# pir.net
KiCad netlist of a schematic drawn in Altium Designer
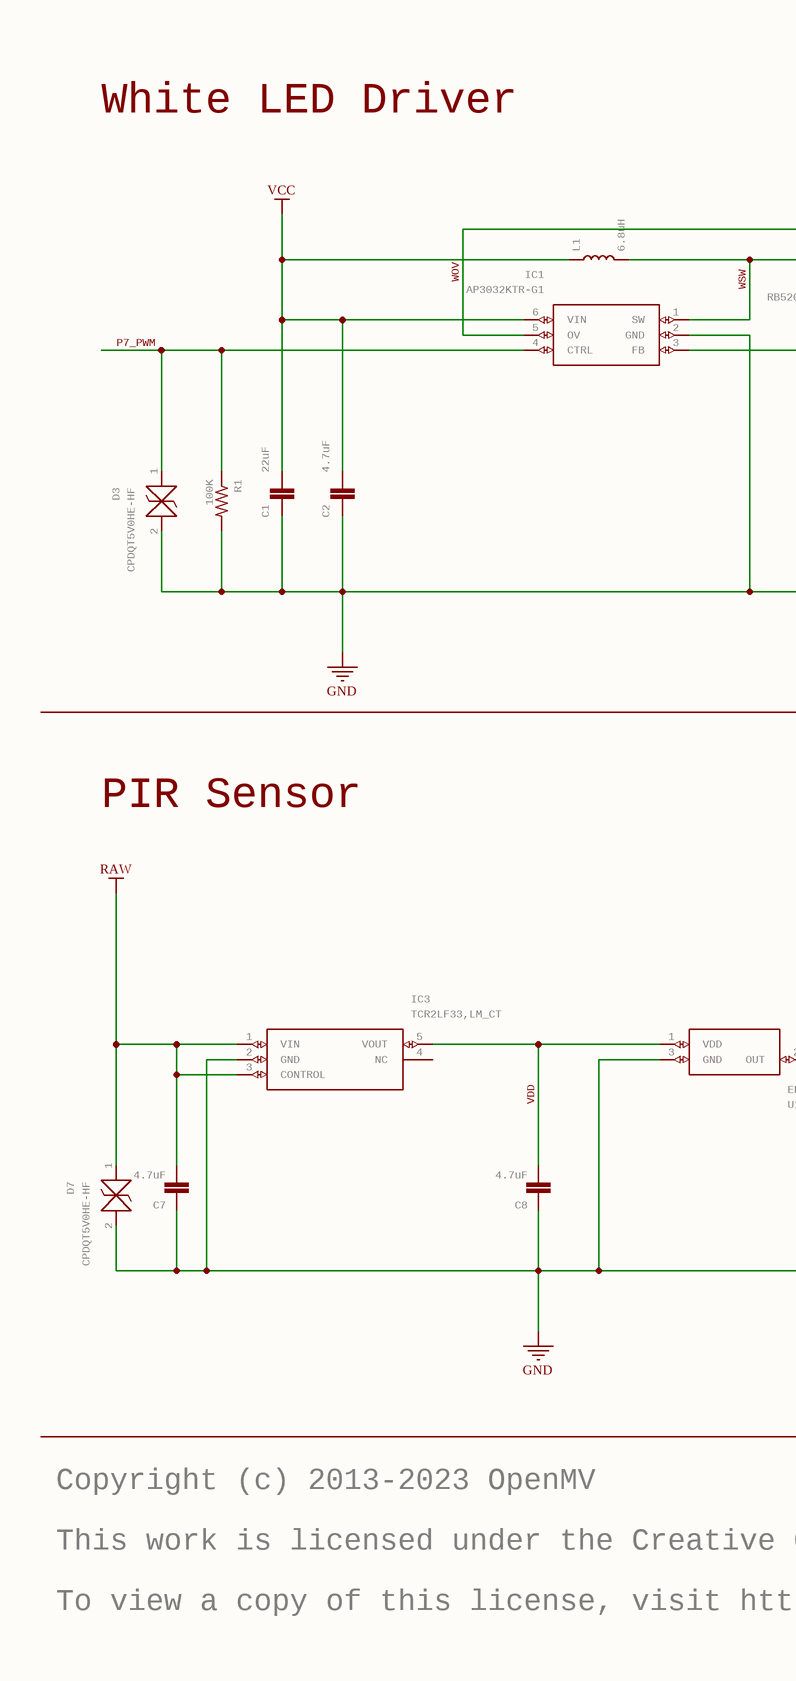
[diagram p0: pir.SchDoc, left]
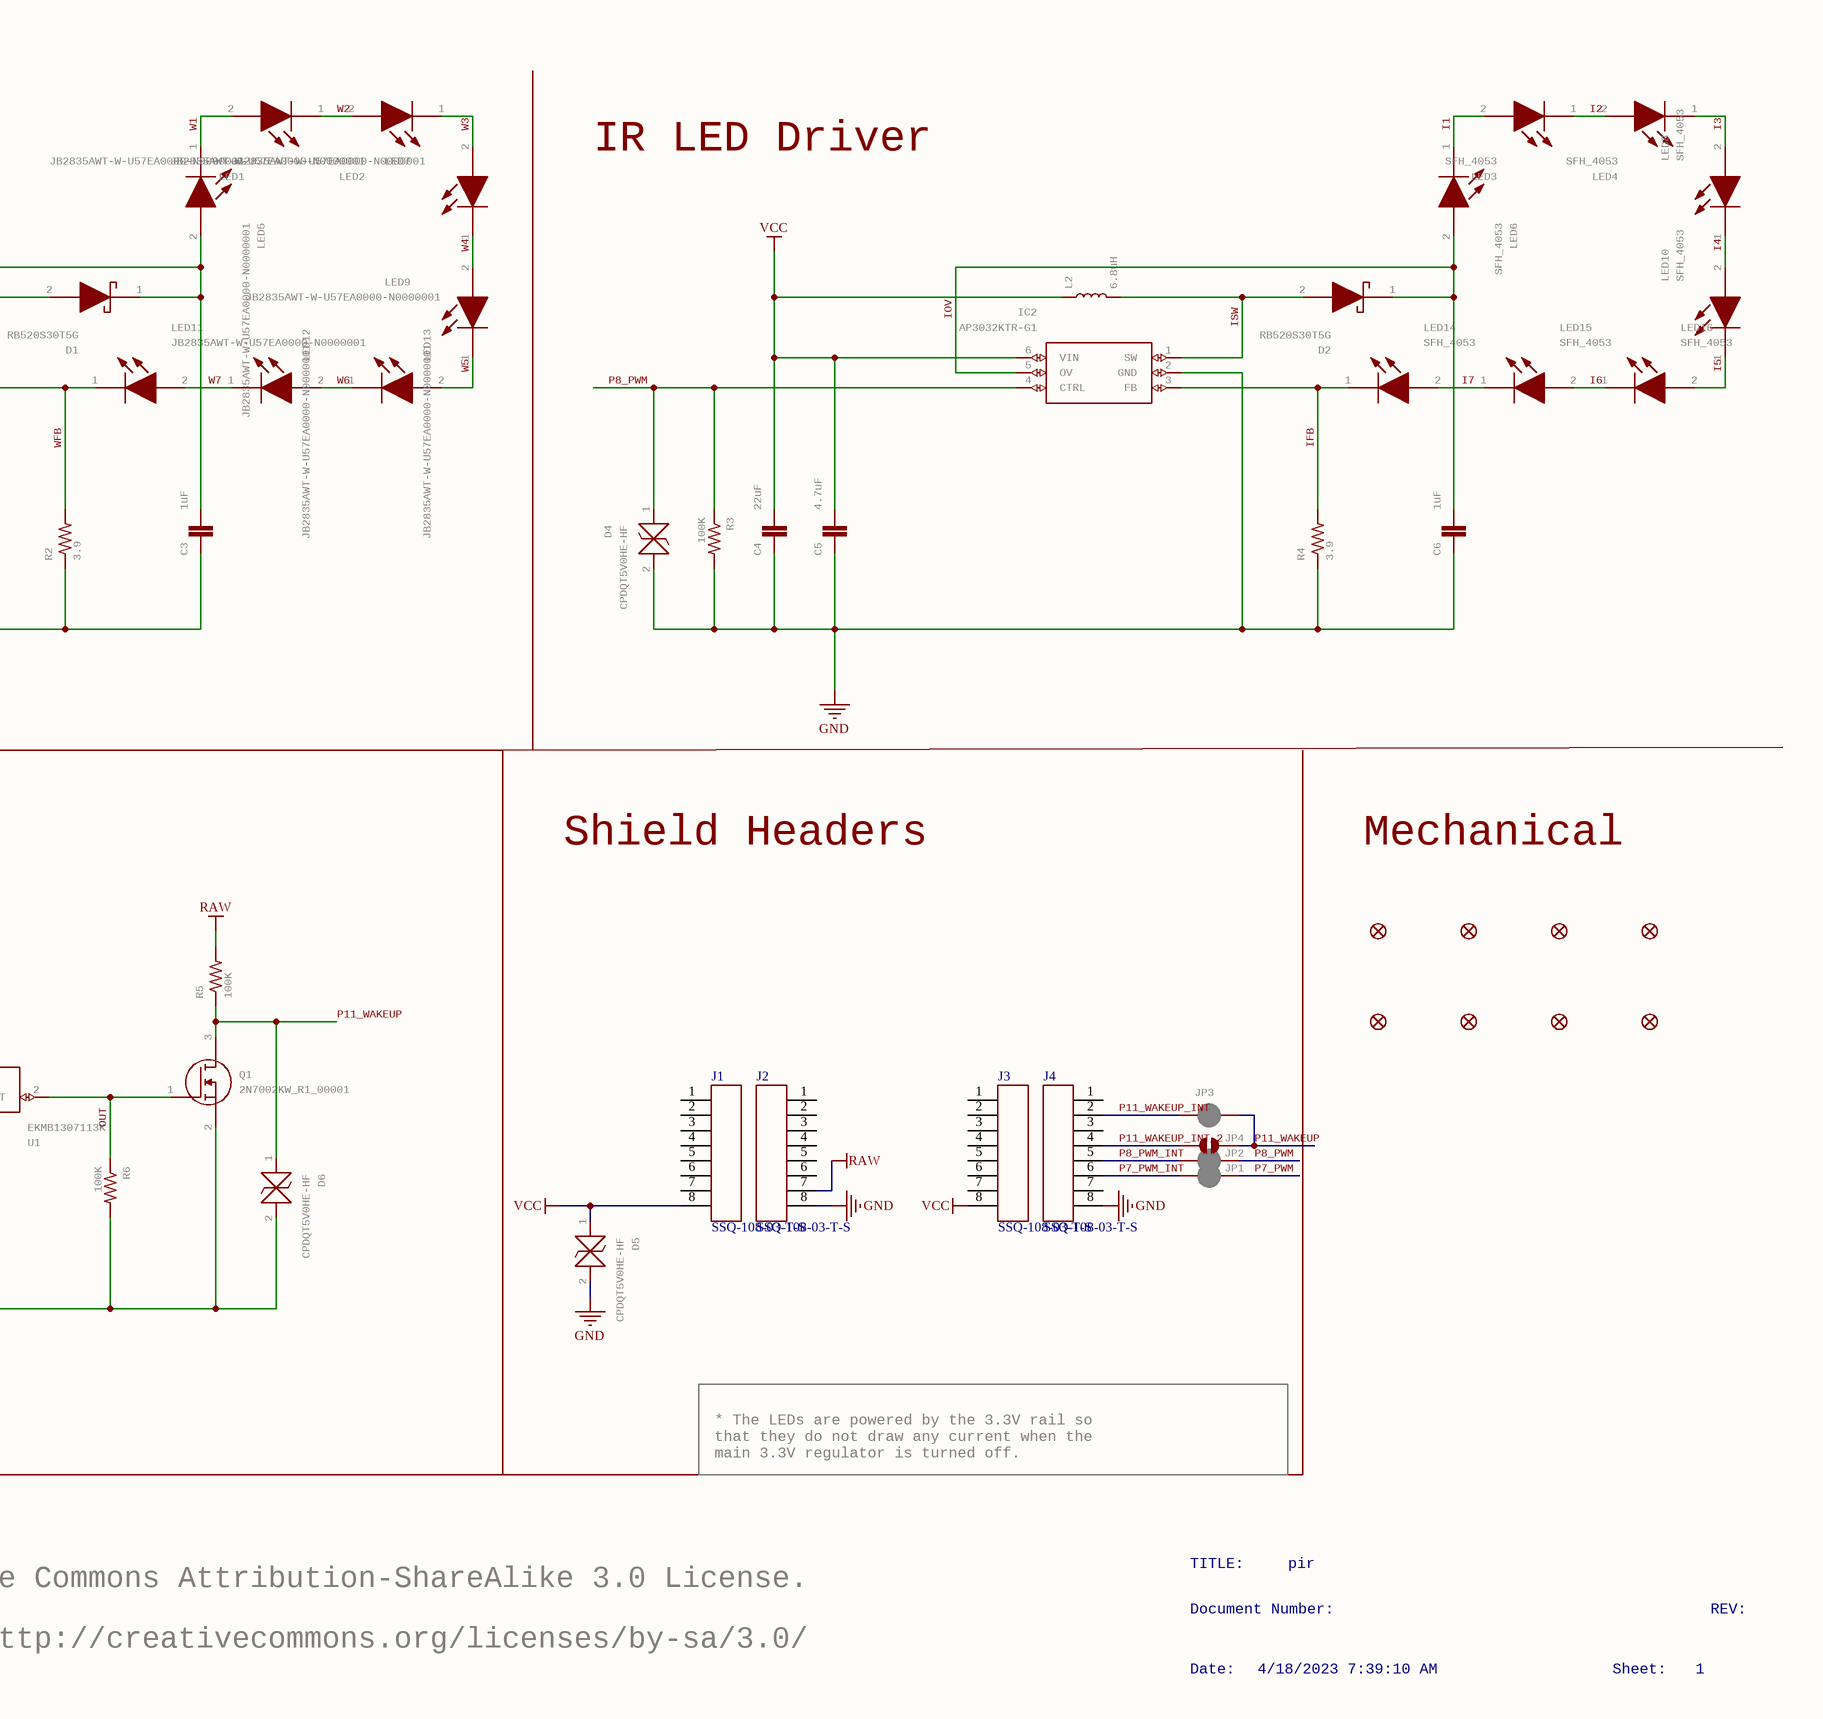
[diagram p1: pir.SchDoc, right]

(export (version "E")
  (design (tool "Eeschema 10.0.6"))
  (components
    (comp (ref "C1")
      (value "22uF")
      (footprint "0805")
      (fields (field (name "MPN") "CL21A226MQQNNNE"))
      (libsource (lib "pir") (part "22UF-0805-6.3V-20%"))
    )
    (comp (ref "C2")
      (value "4.7uF")
      (footprint "0402-CAP")
      (description "CapacitorStandard 0603 ceramic capacitor, and 0.1\" leaded capacitor.")
      (fields (field (name "MPN") "JMK105BBJ475MV-F"))
      (libsource (lib "pir") (part "CAP0402-CAP"))
    )
    (comp (ref "C3")
      (value "1uF")
      (footprint "0402-CAP")
      (description "CapacitorStandard 0603 ceramic capacitor, and 0.1\" leaded capacitor.")
      (fields (field (name "MPN") "GRM155R6YA105KE11D"))
      (libsource (lib "pir") (part "CAP0402-CAP"))
    )
    (comp (ref "C4")
      (value "22uF")
      (footprint "0805")
      (fields (field (name "MPN") "CL21A226MQQNNNE"))
      (libsource (lib "pir") (part "22UF-0805-6.3V-20%"))
    )
    (comp (ref "C5")
      (value "4.7uF")
      (footprint "0402-CAP")
      (description "CapacitorStandard 0603 ceramic capacitor, and 0.1\" leaded capacitor.")
      (fields (field (name "MPN") "JMK105BBJ475MV-F"))
      (libsource (lib "pir") (part "CAP0402-CAP"))
    )
    (comp (ref "C6")
      (value "1uF")
      (footprint "0402-CAP")
      (description "CapacitorStandard 0603 ceramic capacitor, and 0.1\" leaded capacitor.")
      (fields (field (name "MPN") "GRM155R6YA105KE11D"))
      (libsource (lib "pir") (part "CAP0402-CAP"))
    )
    (comp (ref "C7")
      (value "4.7uF")
      (footprint "0402-CAP")
      (description "CapacitorStandard 0603 ceramic capacitor, and 0.1\" leaded capacitor.")
      (fields (field (name "MPN") "JMK105BBJ475MV-F"))
      (libsource (lib "pir") (part "CAP0402-CAP"))
    )
    (comp (ref "C8")
      (value "4.7uF")
      (footprint "0402-CAP")
      (description "CapacitorStandard 0603 ceramic capacitor, and 0.1\" leaded capacitor.")
      (fields (field (name "MPN") "JMK105BBJ475MV-F"))
      (libsource (lib "pir") (part "CAP0402-CAP"))
    )
    (comp (ref "D1")
      (value "RB520S30T5G")
      (footprint "SODFL1608X70N")
      (description "Diode Schottky 30V 0.2A Automotive 2-Pin SOD-523 T/R   Source:  Datasheet")
      (fields (field (name "MOUSER_PART_NUMBER") "863-RB520S30T5G"))
      (libsource (lib "pir") (part "RB520S30T5G"))
    )
    (comp (ref "D2")
      (value "RB520S30T5G")
      (footprint "SODFL1608X70N")
      (description "Diode Schottky 30V 0.2A Automotive 2-Pin SOD-523 T/R   Source:  Datasheet")
      (fields (field (name "MOUSER_PART_NUMBER") "863-RB520S30T5G"))
      (libsource (lib "pir") (part "RB520S30T5G"))
    )
    (comp (ref "D3")
      (value "CPDQT5V0HE-HF")
      (footprint "CPDQT5V0HEHF")
      (description "ESD Suppressors / TVS Diodes DIODE ESD 5VWM 65W 0402/SOD-923F   Source:  Datasheet")
      (fields (field (name "MOUSER_PART_NUMBER") "MOUSER_PART_NUMBER"))
      (libsource (lib "pir") (part "CPDQT5V0HE-HF"))
    )
    (comp (ref "D4")
      (value "CPDQT5V0HE-HF")
      (footprint "CPDQT5V0HEHF")
      (description "ESD Suppressors / TVS Diodes DIODE ESD 5VWM 65W 0402/SOD-923F   Source:  Datasheet")
      (fields (field (name "MOUSER_PART_NUMBER") "MOUSER_PART_NUMBER"))
      (libsource (lib "pir") (part "CPDQT5V0HE-HF"))
    )
    (comp (ref "D5")
      (value "CPDQT5V0HE-HF")
      (footprint "CPDQT5V0HEHF")
      (description "ESD Suppressors / TVS Diodes DIODE ESD 5VWM 65W 0402/SOD-923F   Source:  Datasheet")
      (fields (field (name "MOUSER_PART_NUMBER") "MOUSER_PART_NUMBER"))
      (libsource (lib "pir") (part "CPDQT5V0HE-HF"))
    )
    (comp (ref "D6")
      (value "CPDQT5V0HE-HF")
      (footprint "CPDQT5V0HEHF")
      (description "ESD Suppressors / TVS Diodes DIODE ESD 5VWM 65W 0402/SOD-923F   Source:  Datasheet")
      (fields (field (name "MOUSER_PART_NUMBER") "MOUSER_PART_NUMBER"))
      (libsource (lib "pir") (part "CPDQT5V0HE-HF"))
    )
    (comp (ref "D7")
      (value "CPDQT5V0HE-HF")
      (footprint "CPDQT5V0HEHF")
      (description "ESD Suppressors / TVS Diodes DIODE ESD 5VWM 65W 0402/SOD-923F   Source:  Datasheet")
      (fields (field (name "MOUSER_PART_NUMBER") "MOUSER_PART_NUMBER"))
      (libsource (lib "pir") (part "CPDQT5V0HE-HF"))
    )
    (comp (ref "FD1")
      (value "FIDUCIAL1X2")
      (footprint "FIDUCIAL-1X2")
      (fields (field (name "LIBRARYNAME") "SparkFun-Aesthetics"))
      (libsource (lib "pir") (part "FIDUCIAL1X2"))
    )
    (comp (ref "FD2")
      (value "FIDUCIAL1X2")
      (footprint "FIDUCIAL-1X2")
      (fields (field (name "LIBRARYNAME") "SparkFun-Aesthetics"))
      (libsource (lib "pir") (part "FIDUCIAL1X2"))
    )
    (comp (ref "FD3")
      (value "FIDUCIAL1X2")
      (footprint "FIDUCIAL-1X2")
      (fields (field (name "LIBRARYNAME") "SparkFun-Aesthetics"))
      (libsource (lib "pir") (part "FIDUCIAL1X2"))
    )
    (comp (ref "FD4")
      (value "FIDUCIAL1X2")
      (footprint "FIDUCIAL-1X2")
      (fields (field (name "LIBRARYNAME") "SparkFun-Aesthetics"))
      (libsource (lib "pir") (part "FIDUCIAL1X2"))
    )
    (comp (ref "FD5")
      (value "FIDUCIAL1X2")
      (footprint "FIDUCIAL-1X2")
      (fields (field (name "LIBRARYNAME") "SparkFun-Aesthetics"))
      (libsource (lib "pir") (part "FIDUCIAL1X2"))
    )
    (comp (ref "FD6")
      (value "FIDUCIAL1X2")
      (footprint "FIDUCIAL-1X2")
      (fields (field (name "LIBRARYNAME") "SparkFun-Aesthetics"))
      (libsource (lib "pir") (part "FIDUCIAL1X2"))
    )
    (comp (ref "FD7")
      (value "FIDUCIAL1X2")
      (footprint "FIDUCIAL-1X2")
      (fields (field (name "LIBRARYNAME") "SparkFun-Aesthetics"))
      (libsource (lib "pir") (part "FIDUCIAL1X2"))
    )
    (comp (ref "FD8")
      (value "FIDUCIAL1X2")
      (footprint "FIDUCIAL-1X2")
      (fields (field (name "LIBRARYNAME") "SparkFun-Aesthetics"))
      (libsource (lib "pir") (part "FIDUCIAL1X2"))
    )
    (comp (ref "IC1")
      (value "AP3032KTR-G1")
      (footprint "SOT95P280X145-6N")
      (fields (field (name "MOUSER_PART_NUMBER") "621-AP3032KTR-G1"))
      (libsource (lib "pir") (part "AP3032KTR-G1"))
    )
    (comp (ref "IC2")
      (value "AP3032KTR-G1")
      (footprint "SOT95P280X145-6N")
      (fields (field (name "MOUSER_PART_NUMBER") "621-AP3032KTR-G1"))
      (libsource (lib "pir") (part "AP3032KTR-G1"))
    )
    (comp (ref "IC3")
      (value "TCR2LF33,LM_CT")
      (footprint "TCR2LF33LMCT")
      (description "Linear Voltage Regulator IC Positive Fixed 1 Output 200mA SMV   Source:  Datasheet")
      (fields
        (field (name "MANUFACTURER_PART_NUMBER") "TCR2LF33,LM(CT")
        (field (name "MOUSER_PART_NUMBER") "757-TCR2LF33LMCT")
      )
      (libsource (lib "pir") (part "TCR2LF33,LM_CT"))
    )
    (comp (ref "J1") (value "SSQ-108-03-T-S") (footprint "HDR_1X8") (libsource (lib "") (part "HDR_1X8_1")))
    (comp (ref "J2") (value "SSQ-108-03-T-S") (footprint "HDR_1X8") (libsource (lib "pir") (part "HDR_1X8")))
    (comp (ref "J3") (value "SSQ-108-03-T-S") (footprint "HDR_1X8") (libsource (lib "") (part "HDR_1X8_1")))
    (comp (ref "J4") (value "SSQ-108-03-T-S") (footprint "HDR_1X8") (libsource (lib "pir") (part "HDR_1X8")))
    (comp (ref "JP1")
      (value "JUMPER-SMT_2_NC_PASTE_SILK")
      (footprint "SMT-JUMPER_2_NC_PASTE_SILK")
      (libsource (lib "pir") (part "JUMPER-SMT_2_NC_PASTE_SILK"))
    )
    (comp (ref "JP2")
      (value "JUMPER-SMT_2_NC_PASTE_SILK")
      (footprint "SMT-JUMPER_2_NC_PASTE_SILK")
      (libsource (lib "pir") (part "JUMPER-SMT_2_NC_PASTE_SILK"))
    )
    (comp (ref "JP3")
      (value "JUMPER-SMT_2_NC_PASTE_SILK")
      (footprint "SMT-JUMPER_2_NC_PASTE_SILK")
      (libsource (lib "pir") (part "JUMPER-SMT_2_NC_PASTE_SILK"))
    )
    (comp (ref "JP4")
      (value "JUMPER-SMT_2_NO_SILK")
      (footprint "SMT-JUMPER_2_NO_SILK")
      (libsource (lib "pir") (part "JUMPER-SMT_2_NO_SILK"))
    )
    (comp (ref "L1")
      (value "6.8uH")
      (footprint "0805")
      (fields (field (name "MPN") "MLZ2012M6R8WT000") (field (name "LIBRARYNAME") "SparkFun-Coils"))
      (libsource (lib "pir") (part "INDUCTOR-0805-3.3UH"))
    )
    (comp (ref "L2")
      (value "6.8uH")
      (footprint "0805")
      (fields (field (name "MPN") "MLZ2012M6R8WT000") (field (name "LIBRARYNAME") "SparkFun-Coils"))
      (libsource (lib "pir") (part "INDUCTOR-0805-3.3UH"))
    )
    (comp (ref "LED1")
      (value "JB2835AWT-W-U57EA0000-N0000001")
      (footprint "JB2835AWTWU57EA0000N0000001")
      (description "Mid-Power LEDs - White White 5700 K 90-CRI, 2835 Size, W Class   Source:  Datasheet")
      (fields (field (name "MOUSER_PART_NUMBER") "941-JB2835AWTU57EAN"))
      (libsource (lib "pir") (part "JB2835AWT-W-U57EA0000-N0000001"))
    )
    (comp (ref "LED2")
      (value "JB2835AWT-W-U57EA0000-N0000001")
      (footprint "JB2835AWTWU57EA0000N0000001")
      (description "Mid-Power LEDs - White White 5700 K 90-CRI, 2835 Size, W Class   Source:  Datasheet")
      (fields (field (name "MOUSER_PART_NUMBER") "941-JB2835AWTU57EAN"))
      (libsource (lib "pir") (part "JB2835AWT-W-U57EA0000-N0000001"))
    )
    (comp (ref "LED3")
      (value "SFH_4053")
      (footprint "LEDC1005X55N")
      (fields
        (field (name "MANUFACTURER_PART_NUMBER") "SFH 4053")
        (field (name "MOUSER_PART_NUMBER") "720-SFH4053")
      )
      (libsource (lib "pir") (part "SFH_4053"))
    )
    (comp (ref "LED4")
      (value "SFH_4053")
      (footprint "LEDC1005X55N")
      (fields
        (field (name "MANUFACTURER_PART_NUMBER") "SFH 4053")
        (field (name "MOUSER_PART_NUMBER") "720-SFH4053")
      )
      (libsource (lib "pir") (part "SFH_4053"))
    )
    (comp (ref "LED5")
      (value "JB2835AWT-W-U57EA0000-N0000001")
      (footprint "JB2835AWTWU57EA0000N0000001")
      (description "Mid-Power LEDs - White White 5700 K 90-CRI, 2835 Size, W Class   Source:  Datasheet")
      (fields (field (name "MOUSER_PART_NUMBER") "941-JB2835AWTU57EAN"))
      (libsource (lib "pir") (part "JB2835AWT-W-U57EA0000-N0000001"))
    )
    (comp (ref "LED6")
      (value "SFH_4053")
      (footprint "LEDC1005X55N")
      (fields
        (field (name "MANUFACTURER_PART_NUMBER") "SFH 4053")
        (field (name "MOUSER_PART_NUMBER") "720-SFH4053")
      )
      (libsource (lib "pir") (part "SFH_4053"))
    )
    (comp (ref "LED7")
      (value "JB2835AWT-W-U57EA0000-N0000001")
      (footprint "JB2835AWTWU57EA0000N0000001")
      (description "Mid-Power LEDs - White White 5700 K 90-CRI, 2835 Size, W Class   Source:  Datasheet")
      (fields (field (name "MOUSER_PART_NUMBER") "941-JB2835AWTU57EAN"))
      (libsource (lib "pir") (part "JB2835AWT-W-U57EA0000-N0000001"))
    )
    (comp (ref "LED8")
      (value "SFH_4053")
      (footprint "LEDC1005X55N")
      (fields
        (field (name "MANUFACTURER_PART_NUMBER") "SFH 4053")
        (field (name "MOUSER_PART_NUMBER") "720-SFH4053")
      )
      (libsource (lib "pir") (part "SFH_4053"))
    )
    (comp (ref "LED9")
      (value "JB2835AWT-W-U57EA0000-N0000001")
      (footprint "JB2835AWTWU57EA0000N0000001")
      (description "Mid-Power LEDs - White White 5700 K 90-CRI, 2835 Size, W Class   Source:  Datasheet")
      (fields (field (name "MOUSER_PART_NUMBER") "941-JB2835AWTU57EAN"))
      (libsource (lib "pir") (part "JB2835AWT-W-U57EA0000-N0000001"))
    )
    (comp (ref "LED10")
      (value "SFH_4053")
      (footprint "LEDC1005X55N")
      (fields
        (field (name "MANUFACTURER_PART_NUMBER") "SFH 4053")
        (field (name "MOUSER_PART_NUMBER") "720-SFH4053")
      )
      (libsource (lib "pir") (part "SFH_4053"))
    )
    (comp (ref "LED11")
      (value "JB2835AWT-W-U57EA0000-N0000001")
      (footprint "JB2835AWTWU57EA0000N0000001")
      (description "Mid-Power LEDs - White White 5700 K 90-CRI, 2835 Size, W Class   Source:  Datasheet")
      (fields (field (name "MOUSER_PART_NUMBER") "941-JB2835AWTU57EAN"))
      (libsource (lib "pir") (part "JB2835AWT-W-U57EA0000-N0000001"))
    )
    (comp (ref "LED12")
      (value "JB2835AWT-W-U57EA0000-N0000001")
      (footprint "JB2835AWTWU57EA0000N0000001")
      (description "Mid-Power LEDs - White White 5700 K 90-CRI, 2835 Size, W Class   Source:  Datasheet")
      (fields (field (name "MOUSER_PART_NUMBER") "941-JB2835AWTU57EAN"))
      (libsource (lib "pir") (part "JB2835AWT-W-U57EA0000-N0000001"))
    )
    (comp (ref "LED13")
      (value "JB2835AWT-W-U57EA0000-N0000001")
      (footprint "JB2835AWTWU57EA0000N0000001")
      (description "Mid-Power LEDs - White White 5700 K 90-CRI, 2835 Size, W Class   Source:  Datasheet")
      (fields (field (name "MOUSER_PART_NUMBER") "941-JB2835AWTU57EAN"))
      (libsource (lib "pir") (part "JB2835AWT-W-U57EA0000-N0000001"))
    )
    (comp (ref "LED14")
      (value "SFH_4053")
      (footprint "LEDC1005X55N")
      (fields
        (field (name "MANUFACTURER_PART_NUMBER") "SFH 4053")
        (field (name "MOUSER_PART_NUMBER") "720-SFH4053")
      )
      (libsource (lib "pir") (part "SFH_4053"))
    )
    (comp (ref "LED15")
      (value "SFH_4053")
      (footprint "LEDC1005X55N")
      (fields
        (field (name "MANUFACTURER_PART_NUMBER") "SFH 4053")
        (field (name "MOUSER_PART_NUMBER") "720-SFH4053")
      )
      (libsource (lib "pir") (part "SFH_4053"))
    )
    (comp (ref "LED16")
      (value "SFH_4053")
      (footprint "LEDC1005X55N")
      (fields
        (field (name "MANUFACTURER_PART_NUMBER") "SFH 4053")
        (field (name "MOUSER_PART_NUMBER") "720-SFH4053")
      )
      (libsource (lib "pir") (part "SFH_4053"))
    )
    (comp (ref "Q1")
      (value "2N7002KW_R1_00001")
      (footprint "SOT65P210X110-3N")
      (description "MOSFET 60V N-Channel Enhancement Mode MOSFET - ESD Protected   Source:  Datasheet")
      (fields (field (name "MOUSER_PART_NUMBER") "241-2N7002KWR100001"))
      (libsource (lib "pir") (part "2N7002KW_R1_00001"))
    )
    (comp (ref "R1")
      (value "100K")
      (footprint "0402-RES")
      (description "ResistorBasic schematic elements and footprints for 0603, 1206, and PTH resistors.")
      (fields (field (name "MPN") "AC0402FR-07100KL"))
      (libsource (lib "pir") (part "RESISTOR0402-RES"))
    )
    (comp (ref "R2")
      (value "3.9")
      (footprint "R2512")
      (description "RESISTOR, American symbol")
      (fields (field (name "MPN") "35203R9JT"))
      (libsource (lib "pir") (part "R-US_R2512"))
    )
    (comp (ref "R3")
      (value "100K")
      (footprint "0402-RES")
      (description "ResistorBasic schematic elements and footprints for 0603, 1206, and PTH resistors.")
      (fields (field (name "MPN") "AC0402FR-07100KL"))
      (libsource (lib "pir") (part "RESISTOR0402-RES"))
    )
    (comp (ref "R4")
      (value "3.9")
      (footprint "R2512")
      (description "RESISTOR, American symbol")
      (fields (field (name "MPN") "35203R9JT"))
      (libsource (lib "pir") (part "R-US_R2512"))
    )
    (comp (ref "R5")
      (value "100K")
      (footprint "0402-RES")
      (description "ResistorBasic schematic elements and footprints for 0603, 1206, and PTH resistors.")
      (fields (field (name "MPN") "AC0402FR-07100KL"))
      (libsource (lib "pir") (part "RESISTOR0402-RES"))
    )
    (comp (ref "R6")
      (value "100K")
      (footprint "0402-RES")
      (description "ResistorBasic schematic elements and footprints for 0603, 1206, and PTH resistors.")
      (fields (field (name "MPN") "AC0402FR-07100KL"))
      (libsource (lib "pir") (part "RESISTOR0402-RES"))
    )
    (comp (ref "U1")
      (value "EKMB1307113K")
      (footprint "EKMB1304111K")
      (description "Sensor PIR (Passive Infrared) 472\" (12m) 39.4'  Module   Source:  Datasheet")
      (fields
        (field (name "MANUFACTURER_PART_NUMBER") "EKMB1304111K")
        (field (name "MOUSER_PART_NUMBER") "769-EKMB1304111K")
      )
      (libsource (lib "pir") (part "EKMB1304111K"))
    )
  )
  (nets
    (net (code "1") (name "/I1") (class "Default")
      (node (ref "LED3") (pin "2") (pinfunction "A_2") (pintype "bidirectional"))
      (node (ref "LED6") (pin "1") (pinfunction "K_1") (pintype "bidirectional"))
    )
    (net (code "2") (name "/I2") (class "Default")
      (node (ref "LED3") (pin "1") (pinfunction "K_1") (pintype "bidirectional"))
      (node (ref "LED4") (pin "2") (pinfunction "A_2") (pintype "bidirectional"))
    )
    (net (code "3") (name "/I3") (class "Default")
      (node (ref "LED4") (pin "1") (pinfunction "K_1") (pintype "bidirectional"))
      (node (ref "LED8") (pin "2") (pinfunction "A_2") (pintype "bidirectional"))
    )
    (net (code "4") (name "/I4") (class "Default")
      (node (ref "LED10") (pin "2") (pinfunction "A_2") (pintype "bidirectional"))
      (node (ref "LED8") (pin "1") (pinfunction "K_1") (pintype "bidirectional"))
    )
    (net (code "5") (name "/I5") (class "Default")
      (node (ref "LED10") (pin "1") (pinfunction "K_1") (pintype "bidirectional"))
      (node (ref "LED16") (pin "2") (pinfunction "A_2") (pintype "bidirectional"))
    )
    (net (code "6") (name "/I6") (class "Default")
      (node (ref "LED15") (pin "2") (pinfunction "A_2") (pintype "bidirectional"))
      (node (ref "LED16") (pin "1") (pinfunction "K_1") (pintype "bidirectional"))
    )
    (net (code "7") (name "/I7") (class "Default")
      (node (ref "LED14") (pin "2") (pinfunction "A_2") (pintype "bidirectional"))
      (node (ref "LED15") (pin "1") (pinfunction "K_1") (pintype "bidirectional"))
    )
    (net (code "8") (name "/IFB") (class "Default")
      (node (ref "IC2") (pin "3") (pinfunction "FB_3") (pintype "bidirectional"))
      (node (ref "LED14") (pin "1") (pinfunction "K_1") (pintype "bidirectional"))
      (node (ref "R4") (pin "2") (pinfunction "2_2") (pintype "passive"))
    )
    (net (code "9") (name "/IOV") (class "Default")
      (node (ref "C6") (pin "2") (pinfunction "2_2") (pintype "passive"))
      (node (ref "D2") (pin "1") (pinfunction "K_1") (pintype "bidirectional"))
      (node (ref "IC2") (pin "5") (pinfunction "OV_5") (pintype "bidirectional"))
      (node (ref "LED6") (pin "2") (pinfunction "A_2") (pintype "bidirectional"))
    )
    (net (code "10") (name "/ISW") (class "Default")
      (node (ref "D2") (pin "2") (pinfunction "A_2") (pintype "bidirectional"))
      (node (ref "IC2") (pin "1") (pinfunction "SW_1") (pintype "bidirectional"))
      (node (ref "L2") (pin "2") (pinfunction "2_2") (pintype "passive"))
    )
    (net (code "11") (name "/OUT") (class "Default")
      (node (ref "Q1") (pin "1") (pinfunction "G_1") (pintype "bidirectional"))
      (node (ref "R6") (pin "1") (pinfunction "1_1") (pintype "passive"))
      (node (ref "U1") (pin "2") (pinfunction "OUT_2") (pintype "bidirectional"))
    )
    (net (code "12") (name "/P7_PWM") (class "Default")
      (node (ref "D3") (pin "1") (pinfunction "1_1") (pintype "bidirectional"))
      (node (ref "IC1") (pin "4") (pinfunction "CTRL_4") (pintype "bidirectional"))
      (node (ref "JP1") (pin "2") (pinfunction "2_2") (pintype "passive"))
      (node (ref "R1") (pin "1") (pinfunction "1_1") (pintype "passive"))
    )
    (net (code "13") (name "/P7_PWM_INT") (class "Default")
      (node (ref "J4") (pin "6") (pintype "passive"))
      (node (ref "JP1") (pin "1") (pinfunction "1_1") (pintype "passive"))
    )
    (net (code "14") (name "/P8_PWM") (class "Default")
      (node (ref "D4") (pin "1") (pinfunction "1_1") (pintype "bidirectional"))
      (node (ref "IC2") (pin "4") (pinfunction "CTRL_4") (pintype "bidirectional"))
      (node (ref "JP2") (pin "2") (pinfunction "2_2") (pintype "passive"))
      (node (ref "R3") (pin "1") (pinfunction "1_1") (pintype "passive"))
    )
    (net (code "15") (name "/P8_PWM_INT") (class "Default")
      (node (ref "J4") (pin "5") (pintype "passive"))
      (node (ref "JP2") (pin "1") (pinfunction "1_1") (pintype "passive"))
    )
    (net (code "16") (name "/P11_WAKEUP") (class "Default")
      (node (ref "D6") (pin "1") (pinfunction "1_1") (pintype "bidirectional"))
      (node (ref "JP3") (pin "2") (pinfunction "2_2") (pintype "passive"))
      (node (ref "JP4") (pin "2") (pinfunction "2_2") (pintype "passive"))
      (node (ref "Q1") (pin "3") (pinfunction "D_3") (pintype "bidirectional"))
      (node (ref "R5") (pin "1") (pinfunction "1_1") (pintype "passive"))
    )
    (net (code "17") (name "/P11_WAKEUP_INT") (class "Default")
      (node (ref "J4") (pin "2") (pintype "passive"))
      (node (ref "JP3") (pin "1") (pinfunction "1_1") (pintype "passive"))
    )
    (net (code "18") (name "/P11_WAKEUP_INT_2") (class "Default")
      (node (ref "J4") (pin "4") (pintype "passive"))
      (node (ref "JP4") (pin "1") (pinfunction "1_1") (pintype "passive"))
    )
    (net (code "19") (name "/VDD") (class "Default")
      (node (ref "C8") (pin "2") (pinfunction "2_2") (pintype "passive"))
      (node (ref "IC3") (pin "5") (pinfunction "VOUT_5") (pintype "bidirectional"))
      (node (ref "U1") (pin "1") (pinfunction "VDD_1") (pintype "bidirectional"))
    )
    (net (code "20") (name "/W1") (class "Default")
      (node (ref "LED1") (pin "2") (pinfunction "A_2") (pintype "bidirectional"))
      (node (ref "LED5") (pin "1") (pinfunction "K_1") (pintype "bidirectional"))
    )
    (net (code "21") (name "/W2") (class "Default")
      (node (ref "LED1") (pin "1") (pinfunction "K_1") (pintype "bidirectional"))
      (node (ref "LED2") (pin "2") (pinfunction "A_2") (pintype "bidirectional"))
    )
    (net (code "22") (name "/W3") (class "Default")
      (node (ref "LED2") (pin "1") (pinfunction "K_1") (pintype "bidirectional"))
      (node (ref "LED7") (pin "2") (pinfunction "A_2") (pintype "bidirectional"))
    )
    (net (code "23") (name "/W4") (class "Default")
      (node (ref "LED7") (pin "1") (pinfunction "K_1") (pintype "bidirectional"))
      (node (ref "LED9") (pin "2") (pinfunction "A_2") (pintype "bidirectional"))
    )
    (net (code "24") (name "/W5") (class "Default")
      (node (ref "LED13") (pin "2") (pinfunction "A_2") (pintype "bidirectional"))
      (node (ref "LED9") (pin "1") (pinfunction "K_1") (pintype "bidirectional"))
    )
    (net (code "25") (name "/W6") (class "Default")
      (node (ref "LED12") (pin "2") (pinfunction "A_2") (pintype "bidirectional"))
      (node (ref "LED13") (pin "1") (pinfunction "K_1") (pintype "bidirectional"))
    )
    (net (code "26") (name "/W7") (class "Default")
      (node (ref "LED11") (pin "2") (pinfunction "A_2") (pintype "bidirectional"))
      (node (ref "LED12") (pin "1") (pinfunction "K_1") (pintype "bidirectional"))
    )
    (net (code "27") (name "/WFB") (class "Default")
      (node (ref "IC1") (pin "3") (pinfunction "FB_3") (pintype "bidirectional"))
      (node (ref "LED11") (pin "1") (pinfunction "K_1") (pintype "bidirectional"))
      (node (ref "R2") (pin "2") (pinfunction "2_2") (pintype "passive"))
    )
    (net (code "28") (name "/WOV") (class "Default")
      (node (ref "C3") (pin "2") (pinfunction "2_2") (pintype "passive"))
      (node (ref "D1") (pin "1") (pinfunction "K_1") (pintype "bidirectional"))
      (node (ref "IC1") (pin "5") (pinfunction "OV_5") (pintype "bidirectional"))
      (node (ref "LED5") (pin "2") (pinfunction "A_2") (pintype "bidirectional"))
    )
    (net (code "29") (name "/WSW") (class "Default")
      (node (ref "D1") (pin "2") (pinfunction "A_2") (pintype "bidirectional"))
      (node (ref "IC1") (pin "1") (pinfunction "SW_1") (pintype "bidirectional"))
      (node (ref "L1") (pin "2") (pinfunction "2_2") (pintype "passive"))
    )
    (net (code "30") (name "GND") (class "Default")
      (node (ref "C1") (pin "1") (pinfunction "1_1") (pintype "passive"))
      (node (ref "C2") (pin "1") (pinfunction "1_1") (pintype "passive"))
      (node (ref "C3") (pin "1") (pinfunction "1_1") (pintype "passive"))
      (node (ref "C4") (pin "1") (pinfunction "1_1") (pintype "passive"))
      (node (ref "C5") (pin "1") (pinfunction "1_1") (pintype "passive"))
      (node (ref "C6") (pin "1") (pinfunction "1_1") (pintype "passive"))
      (node (ref "C7") (pin "1") (pinfunction "1_1") (pintype "passive"))
      (node (ref "C8") (pin "1") (pinfunction "1_1") (pintype "passive"))
      (node (ref "D3") (pin "2") (pinfunction "2_2") (pintype "bidirectional"))
      (node (ref "D4") (pin "2") (pinfunction "2_2") (pintype "bidirectional"))
      (node (ref "D5") (pin "2") (pinfunction "2_2") (pintype "bidirectional"))
      (node (ref "D6") (pin "2") (pinfunction "2_2") (pintype "bidirectional"))
      (node (ref "D7") (pin "2") (pinfunction "2_2") (pintype "bidirectional"))
      (node (ref "IC1") (pin "2") (pinfunction "GND_2") (pintype "bidirectional"))
      (node (ref "IC2") (pin "2") (pinfunction "GND_2") (pintype "bidirectional"))
      (node (ref "IC3") (pin "2") (pinfunction "GND_2") (pintype "bidirectional"))
      (node (ref "J2") (pin "8") (pintype "passive"))
      (node (ref "J4") (pin "8") (pintype "passive"))
      (node (ref "Q1") (pin "2") (pinfunction "S_2") (pintype "bidirectional"))
      (node (ref "R1") (pin "2") (pinfunction "2_2") (pintype "passive"))
      (node (ref "R2") (pin "1") (pinfunction "1_1") (pintype "passive"))
      (node (ref "R3") (pin "2") (pinfunction "2_2") (pintype "passive"))
      (node (ref "R4") (pin "1") (pinfunction "1_1") (pintype "passive"))
      (node (ref "R6") (pin "2") (pinfunction "2_2") (pintype "passive"))
      (node (ref "U1") (pin "3") (pinfunction "GND_3") (pintype "bidirectional"))
    )
    (net (code "31") (name "RAW") (class "Default")
      (node (ref "C7") (pin "2") (pinfunction "2_2") (pintype "passive"))
      (node (ref "D7") (pin "1") (pinfunction "1_1") (pintype "bidirectional"))
      (node (ref "IC3") (pin "1") (pinfunction "VIN_1") (pintype "bidirectional"))
      (node (ref "IC3") (pin "3") (pinfunction "CONTROL_3") (pintype "bidirectional"))
      (node (ref "J2") (pin "7") (pintype "passive"))
      (node (ref "R5") (pin "2") (pinfunction "2_2") (pintype "passive"))
    )
    (net (code "32") (name "VCC") (class "Default")
      (node (ref "C1") (pin "2") (pinfunction "2_2") (pintype "passive"))
      (node (ref "C2") (pin "2") (pinfunction "2_2") (pintype "passive"))
      (node (ref "C4") (pin "2") (pinfunction "2_2") (pintype "passive"))
      (node (ref "C5") (pin "2") (pinfunction "2_2") (pintype "passive"))
      (node (ref "D5") (pin "1") (pinfunction "1_1") (pintype "bidirectional"))
      (node (ref "IC1") (pin "6") (pinfunction "VIN_6") (pintype "bidirectional"))
      (node (ref "IC2") (pin "6") (pinfunction "VIN_6") (pintype "bidirectional"))
      (node (ref "J1") (pin "8") (pintype "passive"))
      (node (ref "J3") (pin "8") (pintype "passive"))
      (node (ref "L1") (pin "1") (pinfunction "1_1") (pintype "passive"))
      (node (ref "L2") (pin "1") (pinfunction "1_1") (pintype "passive"))
    )
    (net (code "33") (name "unconnected-(IC3-NC-Pad4)") (class "Default")
      (node (ref "IC3") (pin "4") (pinfunction "NC_4") (pintype "passive"))
    )
    (net (code "34") (name "unconnected-(J1-Pad1)") (class "Default")
      (node (ref "J1") (pin "1") (pintype "passive"))
    )
    (net (code "35") (name "unconnected-(J1-Pad2)") (class "Default")
      (node (ref "J1") (pin "2") (pintype "passive"))
    )
    (net (code "36") (name "unconnected-(J1-Pad3)") (class "Default")
      (node (ref "J1") (pin "3") (pintype "passive"))
    )
    (net (code "37") (name "unconnected-(J1-Pad4)") (class "Default")
      (node (ref "J1") (pin "4") (pintype "passive"))
    )
    (net (code "38") (name "unconnected-(J1-Pad5)") (class "Default")
      (node (ref "J1") (pin "5") (pintype "passive"))
    )
    (net (code "39") (name "unconnected-(J1-Pad6)") (class "Default")
      (node (ref "J1") (pin "6") (pintype "passive"))
    )
    (net (code "40") (name "unconnected-(J1-Pad7)") (class "Default")
      (node (ref "J1") (pin "7") (pintype "passive"))
    )
    (net (code "41") (name "unconnected-(J2-Pad1)") (class "Default")
      (node (ref "J2") (pin "1") (pintype "passive"))
    )
    (net (code "42") (name "unconnected-(J2-Pad2)") (class "Default")
      (node (ref "J2") (pin "2") (pintype "passive"))
    )
    (net (code "43") (name "unconnected-(J2-Pad3)") (class "Default")
      (node (ref "J2") (pin "3") (pintype "passive"))
    )
    (net (code "44") (name "unconnected-(J2-Pad4)") (class "Default")
      (node (ref "J2") (pin "4") (pintype "passive"))
    )
    (net (code "45") (name "unconnected-(J2-Pad5)") (class "Default")
      (node (ref "J2") (pin "5") (pintype "passive"))
    )
    (net (code "46") (name "unconnected-(J2-Pad6)") (class "Default")
      (node (ref "J2") (pin "6") (pintype "passive"))
    )
    (net (code "47") (name "unconnected-(J3-Pad1)") (class "Default")
      (node (ref "J3") (pin "1") (pintype "passive"))
    )
    (net (code "48") (name "unconnected-(J3-Pad2)") (class "Default")
      (node (ref "J3") (pin "2") (pintype "passive"))
    )
    (net (code "49") (name "unconnected-(J3-Pad3)") (class "Default")
      (node (ref "J3") (pin "3") (pintype "passive"))
    )
    (net (code "50") (name "unconnected-(J3-Pad4)") (class "Default")
      (node (ref "J3") (pin "4") (pintype "passive"))
    )
    (net (code "51") (name "unconnected-(J3-Pad5)") (class "Default")
      (node (ref "J3") (pin "5") (pintype "passive"))
    )
    (net (code "52") (name "unconnected-(J3-Pad6)") (class "Default")
      (node (ref "J3") (pin "6") (pintype "passive"))
    )
    (net (code "53") (name "unconnected-(J3-Pad7)") (class "Default")
      (node (ref "J3") (pin "7") (pintype "passive"))
    )
    (net (code "54") (name "unconnected-(J4-Pad1)") (class "Default")
      (node (ref "J4") (pin "1") (pintype "passive"))
    )
    (net (code "55") (name "unconnected-(J4-Pad3)") (class "Default")
      (node (ref "J4") (pin "3") (pintype "passive"))
    )
    (net (code "56") (name "unconnected-(J4-Pad7)") (class "Default")
      (node (ref "J4") (pin "7") (pintype "passive"))
    )
  )
)
